# BD0004.net
KiCad netlist of a schematic drawn in EAGLE
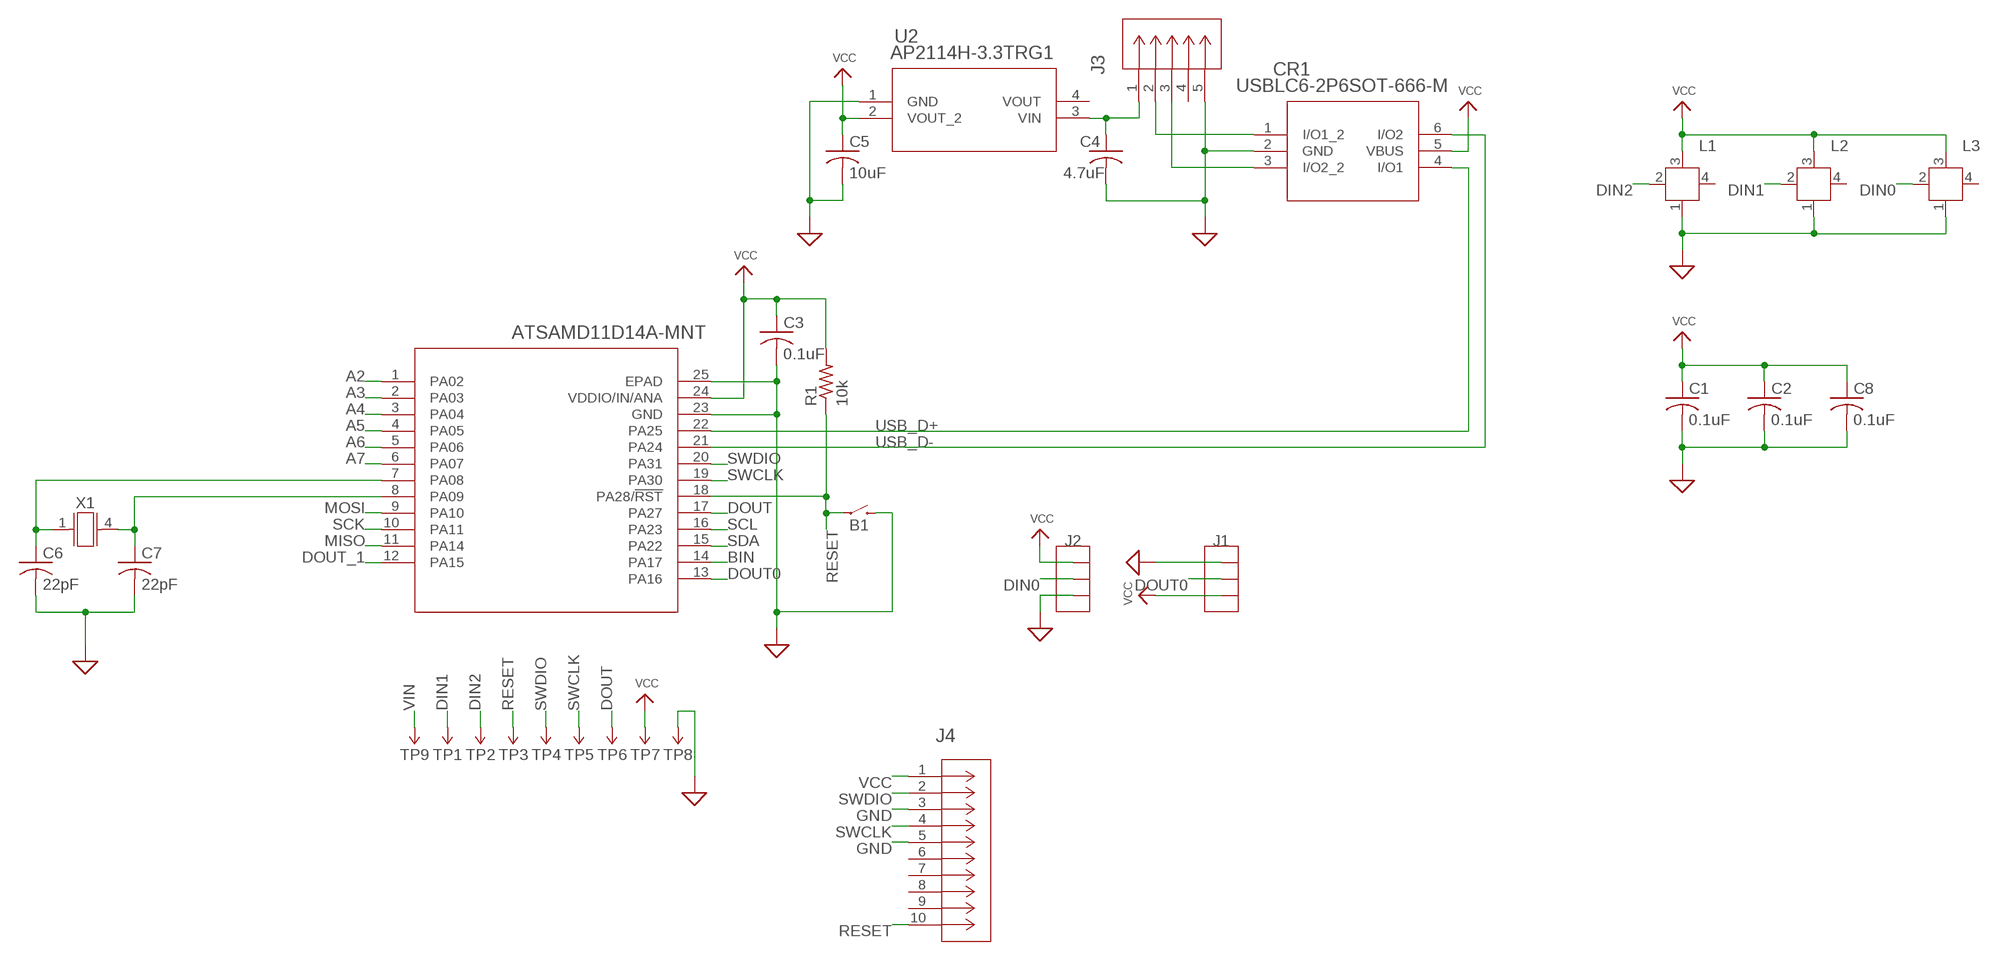
[diagram p0: schematic, sheet 1]

(export (version "E")
  (design (tool "Eeschema 10.0.6"))
  (components
    (comp (ref "B1")
      (value "EVQ-P7A01P")
      (footprint "eagle-import:4-SMD_BUTTON")
      (libsource (lib "eagle-import") (part "EVQ-P7A01P"))
    )
    (comp (ref "C1")
      (value "0.1uF")
      (footprint "eagle-import:C0402")
      (libsource (lib "eagle-import") (part "C-USC0402"))
    )
    (comp (ref "C2")
      (value "0.1uF")
      (footprint "eagle-import:C0402")
      (libsource (lib "eagle-import") (part "C-USC0402"))
    )
    (comp (ref "C3")
      (value "0.1uF")
      (footprint "eagle-import:C0402")
      (libsource (lib "eagle-import") (part "C-USC0402"))
    )
    (comp (ref "C4")
      (value "4.7uF")
      (footprint "eagle-import:C0805")
      (libsource (lib "eagle-import") (part "C-USC0805"))
    )
    (comp (ref "C5")
      (value "10uF")
      (footprint "eagle-import:C0805")
      (libsource (lib "eagle-import") (part "C-USC0805"))
    )
    (comp (ref "C6")
      (value "22pF")
      (footprint "eagle-import:C0402")
      (libsource (lib "eagle-import") (part "C-USC0402"))
    )
    (comp (ref "C7")
      (value "22pF")
      (footprint "eagle-import:C0402")
      (libsource (lib "eagle-import") (part "C-USC0402"))
    )
    (comp (ref "C8")
      (value "0.1uF")
      (footprint "eagle-import:C0402")
      (libsource (lib "eagle-import") (part "C-USC0402"))
    )
    (comp (ref "CR1")
      (value "USBLC6-2P6SOT-666-M")
      (footprint "eagle-import:SOT-666-M")
      (fields (field (name "MANUFACTURER_PART_NUMBER") "USBLC6-2P6"))
      (libsource (lib "eagle-import") (part "USBLC6-2P6SOT-666-M"))
    )
    (comp (ref "J1")
      (value "HEADER_1X3MALE")
      (footprint "eagle-import:M3SMD")
      (libsource (lib "eagle-import") (part "HEADER_1X3MALE"))
    )
    (comp (ref "J2")
      (value "HEADER_1X3FEMALE")
      (footprint "eagle-import:F3SMD")
      (libsource (lib "eagle-import") (part "HEADER_1X3FEMALE"))
    )
    (comp (ref "J3")
      (value "1050171001")
      (footprint "eagle-import:CON00679_5")
      (fields (field (name "COPYRIGHT") "Copyright (C) 2016 Accelerated Designs. All rights reserved"))
      (libsource (lib "eagle-import") (part "1050171001"))
    )
    (comp (ref "J4")
      (value "20021121-00010C4LF")
      (footprint "eagle-import:CONN_00010C4LF")
      (fields (field (name "COPYRIGHT") "Copyright (C) 2018 Accelerated Designs. All rights reserved"))
      (libsource (lib "eagle-import") (part "20021121-00010C4LF"))
    )
    (comp (ref "L1")
      (value "WS2812B")
      (footprint "eagle-import:SK6812")
      (libsource (lib "eagle-import") (part "WS2812B"))
    )
    (comp (ref "L2")
      (value "WS2812B")
      (footprint "eagle-import:SK6812")
      (libsource (lib "eagle-import") (part "WS2812B"))
    )
    (comp (ref "L3")
      (value "WS2812B")
      (footprint "eagle-import:SK6812")
      (libsource (lib "eagle-import") (part "WS2812B"))
    )
    (comp (ref "R1")
      (value "10k")
      (footprint "eagle-import:R0402")
      (libsource (lib "eagle-import") (part "R-US_R0402"))
    )
    (comp (ref "TP1")
      (value "POGO")
      (footprint "eagle-import:R-1-CR")
      (libsource (lib "eagle-import") (part "POGO"))
    )
    (comp (ref "TP2")
      (value "POGO")
      (footprint "eagle-import:R-1-CR")
      (libsource (lib "eagle-import") (part "POGO"))
    )
    (comp (ref "TP3")
      (value "POGO")
      (footprint "eagle-import:R-1-CR")
      (libsource (lib "eagle-import") (part "POGO"))
    )
    (comp (ref "TP4")
      (value "POGO")
      (footprint "eagle-import:R-1-CR")
      (libsource (lib "eagle-import") (part "POGO"))
    )
    (comp (ref "TP5")
      (value "POGO")
      (footprint "eagle-import:R-1-CR")
      (libsource (lib "eagle-import") (part "POGO"))
    )
    (comp (ref "TP6")
      (value "POGO")
      (footprint "eagle-import:R-1-CR")
      (libsource (lib "eagle-import") (part "POGO"))
    )
    (comp (ref "TP7")
      (value "POGO")
      (footprint "eagle-import:R-1-CR")
      (libsource (lib "eagle-import") (part "POGO"))
    )
    (comp (ref "TP8")
      (value "POGO")
      (footprint "eagle-import:R-1-CR")
      (libsource (lib "eagle-import") (part "POGO"))
    )
    (comp (ref "TP9")
      (value "POGO")
      (footprint "eagle-import:R-1-CR")
      (libsource (lib "eagle-import") (part "POGO"))
    )
    (comp (ref "U1")
      (value "ATSAMD11D14A-MNT")
      (footprint "eagle-import:QFN24_4X4MC")
      (fields (field (name "COPYRIGHT") "Copyright (C) 2018 Accelerated Designs. All rights reserved"))
      (libsource (lib "eagle-import") (part "ATSAMD11D14A-MNT"))
    )
    (comp (ref "U2")
      (value "AP2114H-3.3TRG1")
      (footprint "eagle-import:SOT-223")
      (libsource (lib "eagle-import") (part "AP2114H-3.3TRG1"))
    )
    (comp (ref "X1")
      (value "MC-146-32.7680JKA-A0:ROHS")
      (footprint "eagle-import:4-SMD_FLAT_LEADS")
      (libsource (lib "eagle-import") (part "MC-146-32.7680JKA-A0{colon}ROHS"))
    )
  )
  (nets
    (net (code "1") (name "/A2") (class "Default")
      (node (ref "U1") (pin "1") (pinfunction "PA02_1") (pintype "bidirectional"))
    )
    (net (code "2") (name "/A3") (class "Default")
      (node (ref "U1") (pin "2") (pinfunction "PA03_2") (pintype "bidirectional"))
    )
    (net (code "3") (name "/A4") (class "Default")
      (node (ref "U1") (pin "3") (pinfunction "PA04_3") (pintype "bidirectional"))
    )
    (net (code "4") (name "/A5") (class "Default")
      (node (ref "U1") (pin "4") (pinfunction "PA05_4") (pintype "bidirectional"))
    )
    (net (code "5") (name "/A6") (class "Default")
      (node (ref "U1") (pin "5") (pinfunction "PA06_5") (pintype "bidirectional"))
    )
    (net (code "6") (name "/A7") (class "Default")
      (node (ref "U1") (pin "6") (pinfunction "PA07_6") (pintype "bidirectional"))
    )
    (net (code "7") (name "/BIN") (class "Default")
      (node (ref "U1") (pin "14") (pinfunction "PA17_14") (pintype "bidirectional"))
    )
    (net (code "8") (name "/DIN0") (class "Default")
      (node (ref "J2") (pin "2A") (pinfunction "P$2_2A") (pintype "bidirectional"))
      (node (ref "J2") (pin "2B") (pinfunction "P$2_2B") (pintype "bidirectional"))
      (node (ref "L3") (pin "2") (pinfunction "DIN_2") (pintype "bidirectional"))
    )
    (net (code "9") (name "/DIN1") (class "Default")
      (node (ref "L2") (pin "2") (pinfunction "DIN_2") (pintype "bidirectional"))
      (node (ref "TP1") (pin "P$1") (pinfunction "P$1_P$1") (pintype "bidirectional"))
    )
    (net (code "10") (name "/DIN2") (class "Default")
      (node (ref "L1") (pin "2") (pinfunction "DIN_2") (pintype "bidirectional"))
      (node (ref "TP2") (pin "P$1") (pinfunction "P$1_P$1") (pintype "bidirectional"))
    )
    (net (code "11") (name "/DOUT") (class "Default")
      (node (ref "TP6") (pin "P$1") (pinfunction "P$1_P$1") (pintype "bidirectional"))
      (node (ref "U1") (pin "17") (pinfunction "PA27_17") (pintype "bidirectional"))
    )
    (net (code "12") (name "/DOUT0") (class "Default")
      (node (ref "J1") (pin "2") (pinfunction "P$2_2") (pintype "bidirectional"))
      (node (ref "U1") (pin "13") (pinfunction "PA16_13") (pintype "bidirectional"))
    )
    (net (code "13") (name "/DOUT_1") (class "Default")
      (node (ref "U1") (pin "12") (pinfunction "PA15_12") (pintype "bidirectional"))
    )
    (net (code "14") (name "/MISO") (class "Default")
      (node (ref "U1") (pin "11") (pinfunction "PA14_11") (pintype "bidirectional"))
    )
    (net (code "15") (name "/MOSI") (class "Default")
      (node (ref "U1") (pin "9") (pinfunction "PA10_9") (pintype "bidirectional"))
    )
    (net (code "16") (name "/RESET") (class "Default")
      (node (ref "B1") (pin "1A") (pinfunction "P$1_1A") (pintype "bidirectional"))
      (node (ref "B1") (pin "1B") (pinfunction "P$1_1B") (pintype "bidirectional"))
      (node (ref "J4") (pin "10") (pinfunction "10_10") (pintype "passive"))
      (node (ref "R1") (pin "1") (pinfunction "1_1") (pintype "passive"))
      (node (ref "TP3") (pin "P$1") (pinfunction "P$1_P$1") (pintype "bidirectional"))
      (node (ref "U1") (pin "18") (pinfunction "PA28/~{RST}_18") (pintype "bidirectional"))
    )
    (net (code "17") (name "/SCK") (class "Default")
      (node (ref "U1") (pin "10") (pinfunction "PA11_10") (pintype "bidirectional"))
    )
    (net (code "18") (name "/SCL") (class "Default")
      (node (ref "U1") (pin "16") (pinfunction "PA23_16") (pintype "bidirectional"))
    )
    (net (code "19") (name "/SDA") (class "Default")
      (node (ref "U1") (pin "15") (pinfunction "PA22_15") (pintype "bidirectional"))
    )
    (net (code "20") (name "/SWCLK") (class "Default")
      (node (ref "J4") (pin "4") (pinfunction "4_4") (pintype "passive"))
      (node (ref "TP5") (pin "P$1") (pinfunction "P$1_P$1") (pintype "bidirectional"))
      (node (ref "U1") (pin "19") (pinfunction "PA30_19") (pintype "bidirectional"))
    )
    (net (code "21") (name "/SWDIO") (class "Default")
      (node (ref "J4") (pin "2") (pinfunction "2_2") (pintype "passive"))
      (node (ref "TP4") (pin "P$1") (pinfunction "P$1_P$1") (pintype "bidirectional"))
      (node (ref "U1") (pin "20") (pinfunction "PA31_20") (pintype "bidirectional"))
    )
    (net (code "22") (name "/USB_D+") (class "Default")
      (node (ref "CR1") (pin "4") (pinfunction "I/O1_4") (pintype "bidirectional"))
      (node (ref "U1") (pin "22") (pinfunction "PA25_22") (pintype "bidirectional"))
    )
    (net (code "23") (name "/USB_D-") (class "Default")
      (node (ref "CR1") (pin "6") (pinfunction "I/O2_6") (pintype "bidirectional"))
      (node (ref "U1") (pin "21") (pinfunction "PA24_21") (pintype "bidirectional"))
    )
    (net (code "24") (name "/VIN") (class "Default")
      (node (ref "C4") (pin "1") (pinfunction "1_1") (pintype "passive"))
      (node (ref "J3") (pin "1") (pinfunction "1_1") (pintype "passive"))
      (node (ref "TP9") (pin "P$1") (pinfunction "P$1_P$1") (pintype "bidirectional"))
      (node (ref "U2") (pin "3") (pinfunction "VIN_3") (pintype "input"))
    )
    (net (code "25") (name "Net-(CR1-I{slash}O1_2)") (class "Default")
      (node (ref "CR1") (pin "1") (pinfunction "I/O1_2_1") (pintype "bidirectional"))
      (node (ref "J3") (pin "2") (pinfunction "2_2") (pintype "passive"))
    )
    (net (code "26") (name "Net-(CR1-I{slash}O2_2)") (class "Default")
      (node (ref "CR1") (pin "3") (pinfunction "I/O2_2_3") (pintype "bidirectional"))
      (node (ref "J3") (pin "3") (pinfunction "3_3") (pintype "passive"))
    )
    (net (code "27") (name "Net-(U1-PA08)") (class "Default")
      (node (ref "C6") (pin "1") (pinfunction "1_1") (pintype "passive"))
      (node (ref "U1") (pin "7") (pinfunction "PA08_7") (pintype "bidirectional"))
      (node (ref "X1") (pin "1") (pinfunction "P$1_1") (pintype "bidirectional"))
    )
    (net (code "28") (name "Net-(U1-PA09)") (class "Default")
      (node (ref "C7") (pin "1") (pinfunction "1_1") (pintype "passive"))
      (node (ref "U1") (pin "8") (pinfunction "PA09_8") (pintype "bidirectional"))
      (node (ref "X1") (pin "4") (pinfunction "P$2_4") (pintype "bidirectional"))
    )
    (net (code "29") (name "SUP") (class "Default")
      (node (ref "B1") (pin "2A") (pinfunction "P$2_2A") (pintype "bidirectional"))
      (node (ref "B1") (pin "2B") (pinfunction "P$2_2B") (pintype "bidirectional"))
      (node (ref "C1") (pin "2") (pinfunction "2_2") (pintype "passive"))
      (node (ref "C2") (pin "2") (pinfunction "2_2") (pintype "passive"))
      (node (ref "C3") (pin "2") (pinfunction "2_2") (pintype "passive"))
      (node (ref "C4") (pin "2") (pinfunction "2_2") (pintype "passive"))
      (node (ref "C5") (pin "2") (pinfunction "2_2") (pintype "passive"))
      (node (ref "C6") (pin "2") (pinfunction "2_2") (pintype "passive"))
      (node (ref "C7") (pin "2") (pinfunction "2_2") (pintype "passive"))
      (node (ref "C8") (pin "2") (pinfunction "2_2") (pintype "passive"))
      (node (ref "CR1") (pin "2") (pinfunction "GND_2") (pintype "power_in"))
      (node (ref "J1") (pin "1") (pinfunction "P$1_1") (pintype "bidirectional"))
      (node (ref "J2") (pin "3A") (pinfunction "P$3_3A") (pintype "bidirectional"))
      (node (ref "J2") (pin "3B") (pinfunction "P$3_3B") (pintype "bidirectional"))
      (node (ref "J3") (pin "5") (pinfunction "5_5") (pintype "passive"))
      (node (ref "J4") (pin "3") (pinfunction "3_3") (pintype "passive"))
      (node (ref "J4") (pin "5") (pinfunction "5_5") (pintype "passive"))
      (node (ref "L1") (pin "1") (pinfunction "VSS_1") (pintype "bidirectional"))
      (node (ref "L2") (pin "1") (pinfunction "VSS_1") (pintype "bidirectional"))
      (node (ref "L3") (pin "1") (pinfunction "VSS_1") (pintype "bidirectional"))
      (node (ref "TP8") (pin "P$1") (pinfunction "P$1_P$1") (pintype "bidirectional"))
      (node (ref "U1") (pin "23") (pinfunction "GND_23") (pintype "passive"))
      (node (ref "U1") (pin "25") (pinfunction "EPAD_25") (pintype "passive"))
      (node (ref "U2") (pin "1") (pinfunction "GND_1") (pintype "passive"))
    )
    (net (code "30") (name "VCC") (class "Default")
      (node (ref "C1") (pin "1") (pinfunction "1_1") (pintype "passive"))
      (node (ref "C2") (pin "1") (pinfunction "1_1") (pintype "passive"))
      (node (ref "C3") (pin "1") (pinfunction "1_1") (pintype "passive"))
      (node (ref "C5") (pin "1") (pinfunction "1_1") (pintype "passive"))
      (node (ref "C8") (pin "1") (pinfunction "1_1") (pintype "passive"))
      (node (ref "CR1") (pin "5") (pinfunction "VBUS_5") (pintype "power_in"))
      (node (ref "J1") (pin "3") (pinfunction "P$3_3") (pintype "bidirectional"))
      (node (ref "J2") (pin "1A") (pinfunction "P$1_1A") (pintype "bidirectional"))
      (node (ref "J2") (pin "1B") (pinfunction "P$1_1B") (pintype "bidirectional"))
      (node (ref "J4") (pin "1") (pinfunction "1_1") (pintype "passive"))
      (node (ref "L1") (pin "3") (pinfunction "VDD_3") (pintype "bidirectional"))
      (node (ref "L2") (pin "3") (pinfunction "VDD_3") (pintype "bidirectional"))
      (node (ref "L3") (pin "3") (pinfunction "VDD_3") (pintype "bidirectional"))
      (node (ref "R1") (pin "2") (pinfunction "2_2") (pintype "passive"))
      (node (ref "TP7") (pin "P$1") (pinfunction "P$1_P$1") (pintype "bidirectional"))
      (node (ref "U1") (pin "24") (pinfunction "VDDIO/IN/ANA_24") (pintype "power_in"))
      (node (ref "U2") (pin "2") (pinfunction "VOUT_2_2") (pintype "output"))
    )
    (net (code "31") (name "unconnected-(J3-Pad4)") (class "Default")
      (node (ref "J3") (pin "4") (pinfunction "4_4") (pintype "passive"))
    )
    (net (code "32") (name "unconnected-(J4-Pad6)") (class "Default")
      (node (ref "J4") (pin "6") (pinfunction "6_6") (pintype "passive"))
    )
    (net (code "33") (name "unconnected-(J4-Pad7)") (class "Default")
      (node (ref "J4") (pin "7") (pinfunction "7_7") (pintype "passive"))
    )
    (net (code "34") (name "unconnected-(J4-Pad8)") (class "Default")
      (node (ref "J4") (pin "8") (pinfunction "8_8") (pintype "passive"))
    )
    (net (code "35") (name "unconnected-(J4-Pad9)") (class "Default")
      (node (ref "J4") (pin "9") (pinfunction "9_9") (pintype "passive"))
    )
    (net (code "36") (name "unconnected-(L1-DOUT-Pad4)") (class "Default")
      (node (ref "L1") (pin "4") (pinfunction "DOUT_4") (pintype "bidirectional"))
    )
    (net (code "37") (name "unconnected-(L2-DOUT-Pad4)") (class "Default")
      (node (ref "L2") (pin "4") (pinfunction "DOUT_4") (pintype "bidirectional"))
    )
    (net (code "38") (name "unconnected-(L3-DOUT-Pad4)") (class "Default")
      (node (ref "L3") (pin "4") (pinfunction "DOUT_4") (pintype "bidirectional"))
    )
    (net (code "39") (name "unconnected-(U2-VOUT-Pad4)") (class "Default")
      (node (ref "U2") (pin "4") (pinfunction "VOUT_4") (pintype "output"))
    )
  )
)
